# Transitest556-170113.net
KiCad netlist of a schematic drawn in EAGLE
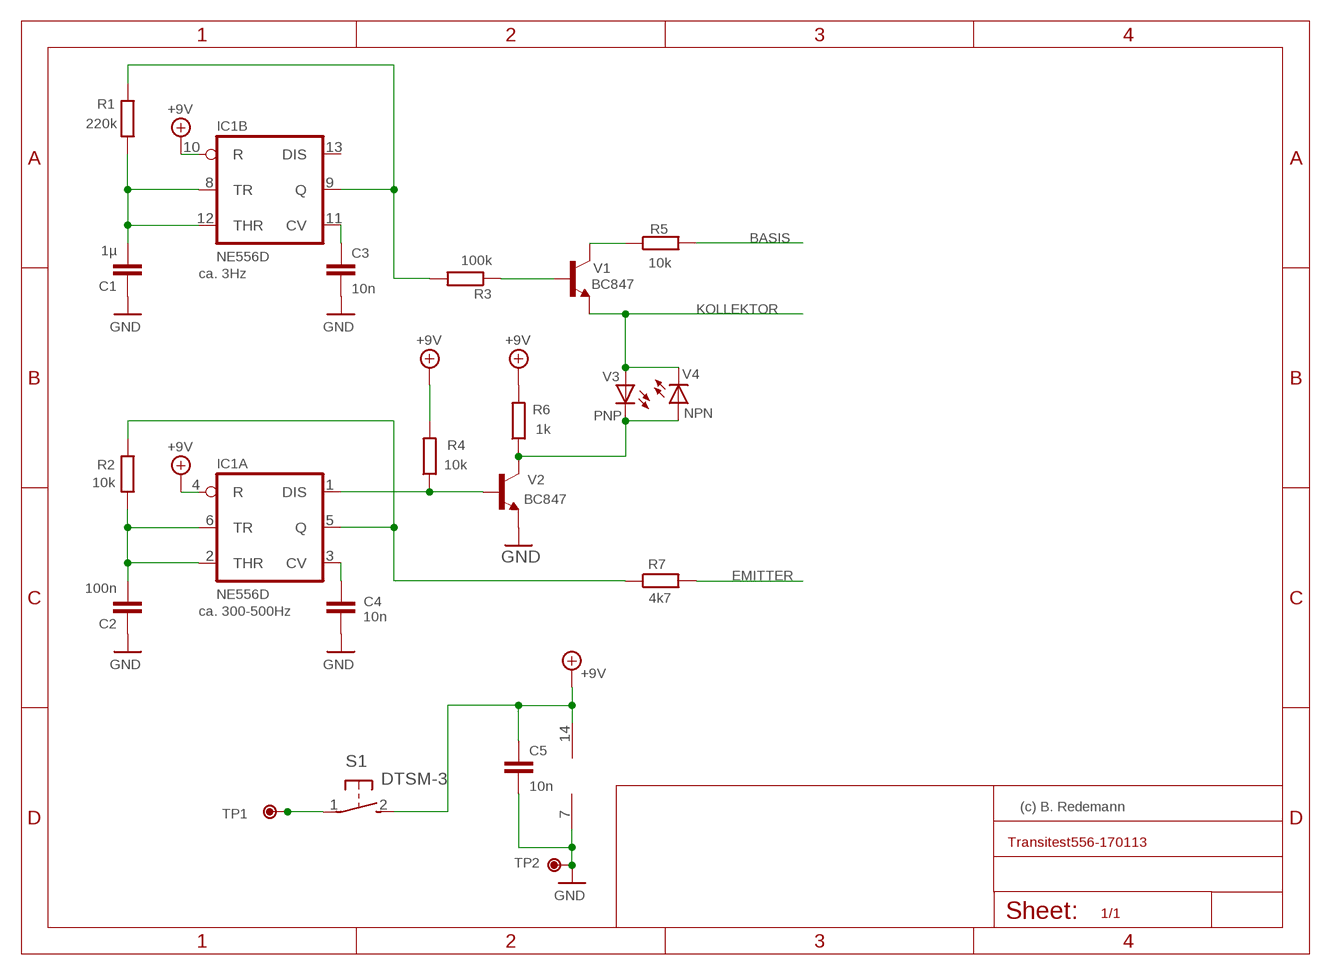
[diagram p0: schematic, sheet 1]

(export (version "E")
  (design (tool "Eeschema 10.0.6"))
  (components
    (comp (ref "C1")
      (value "1µ")
      (footprint "eagle-import:C0805")
      (libsource (lib "eagle-import") (part "C-EUC0805"))
    )
    (comp (ref "C2")
      (value "100n")
      (footprint "eagle-import:C0805")
      (libsource (lib "eagle-import") (part "C-EUC0805"))
    )
    (comp (ref "C3")
      (value "10n")
      (footprint "eagle-import:C0805")
      (libsource (lib "eagle-import") (part "C-EUC0805"))
    )
    (comp (ref "C4")
      (value "10n")
      (footprint "eagle-import:C0805")
      (libsource (lib "eagle-import") (part "C-EUC0805"))
    )
    (comp (ref "C5")
      (value "10n")
      (footprint "eagle-import:C0805")
      (libsource (lib "eagle-import") (part "C-EUC0805"))
    )
    (comp (ref "IC1")
      (value "NE556D")
      (footprint "eagle-import:SO14")
      (libsource (lib "eagle-import") (part "556DNE"))
    )
    (comp (ref "R1")
      (value "220k")
      (footprint "eagle-import:R0805")
      (libsource (lib "eagle-import") (part "R-EU_R0805"))
    )
    (comp (ref "R2")
      (value "10k")
      (footprint "eagle-import:R0805")
      (libsource (lib "eagle-import") (part "R-EU_R0805"))
    )
    (comp (ref "R3")
      (value "100k")
      (footprint "eagle-import:R0805")
      (libsource (lib "eagle-import") (part "R-EU_R0805"))
    )
    (comp (ref "R4")
      (value "10k")
      (footprint "eagle-import:R0805")
      (libsource (lib "eagle-import") (part "R-EU_R0805"))
    )
    (comp (ref "R5")
      (value "10k")
      (footprint "eagle-import:R0805")
      (libsource (lib "eagle-import") (part "R-EU_R0805"))
    )
    (comp (ref "R6")
      (value "1k")
      (footprint "eagle-import:R0805")
      (libsource (lib "eagle-import") (part "R-EU_R0805"))
    )
    (comp (ref "R7")
      (value "4k7")
      (footprint "eagle-import:R0805")
      (libsource (lib "eagle-import") (part "R-EU_R0805"))
    )
    (comp (ref "S1")
      (value "DTSM-3")
      (footprint "eagle-import:DTSM-3")
      (libsource (lib "eagle-import") (part "DTSM-3"))
    )
    (comp (ref "TP1")
      (value "TPPAD1-13")
      (footprint "eagle-import:P1-13")
      (libsource (lib "eagle-import") (part "TPPAD1-13"))
    )
    (comp (ref "TP2")
      (value "TPPAD1-13")
      (footprint "eagle-import:P1-13")
      (libsource (lib "eagle-import") (part "TPPAD1-13"))
    )
    (comp (ref "V1")
      (value "BC847")
      (footprint "eagle-import:SOT23")
      (libsource (lib "eagle-import") (part "BC847"))
    )
    (comp (ref "V2")
      (value "BC847")
      (footprint "eagle-import:SOT23")
      (libsource (lib "eagle-import") (part "BC847"))
    )
    (comp (ref "V3")
      (value "PNP")
      (footprint "eagle-import:CHIP-LED0805")
      (libsource (lib "eagle-import") (part "LEDCHIP-LED0805"))
    )
    (comp (ref "V4")
      (value "NPN")
      (footprint "eagle-import:CHIP-LED0805")
      (libsource (lib "eagle-import") (part "LEDCHIP-LED0805"))
    )
  )
  (nets
    (net (code "1") (name "+9V") (class "Default")
      (node (ref "C5") (pin "1") (pinfunction "1_1") (pintype "passive"))
      (node (ref "IC1") (pin "10") (pinfunction "R_10") (pintype "input"))
      (node (ref "IC1") (pin "14") (pinfunction "V+_14") (pintype "power_in"))
      (node (ref "IC1") (pin "4") (pinfunction "R_4") (pintype "input"))
      (node (ref "R4") (pin "2") (pinfunction "2_2") (pintype "passive"))
      (node (ref "R6") (pin "2") (pinfunction "2_2") (pintype "passive"))
      (node (ref "S1") (pin "2") (pinfunction "2_2") (pintype "passive"))
    )
    (net (code "2") (name "/BASIS") (class "Default")
      (node (ref "R5") (pin "2") (pinfunction "2_2") (pintype "passive"))
    )
    (net (code "3") (name "/EMITTER") (class "Default")
      (node (ref "R7") (pin "2") (pinfunction "2_2") (pintype "passive"))
    )
    (net (code "4") (name "/KOLLEKTOR") (class "Default")
      (node (ref "V1") (pin "2") (pinfunction "E_2") (pintype "passive"))
      (node (ref "V3") (pin "A") (pinfunction "A_A") (pintype "passive"))
      (node (ref "V4") (pin "C") (pinfunction "C_C") (pintype "passive"))
    )
    (net (code "5") (name "GND") (class "Default")
      (node (ref "C1") (pin "1") (pinfunction "1_1") (pintype "passive"))
      (node (ref "C2") (pin "1") (pinfunction "1_1") (pintype "passive"))
      (node (ref "C3") (pin "2") (pinfunction "2_2") (pintype "passive"))
      (node (ref "C4") (pin "1") (pinfunction "1_1") (pintype "passive"))
      (node (ref "C5") (pin "2") (pinfunction "2_2") (pintype "passive"))
      (node (ref "IC1") (pin "7") (pinfunction "GND_7") (pintype "power_in"))
      (node (ref "TP2") (pin "TP") (pinfunction "TP_TP") (pintype "bidirectional"))
      (node (ref "V2") (pin "2") (pinfunction "E_2") (pintype "passive"))
    )
    (net (code "6") (name "Net-(IC1A-CV)") (class "Default")
      (node (ref "C4") (pin "2") (pinfunction "2_2") (pintype "passive"))
      (node (ref "IC1") (pin "3") (pinfunction "CV_3") (pintype "bidirectional"))
    )
    (net (code "7") (name "Net-(IC1A-DIS)") (class "Default")
      (node (ref "IC1") (pin "1") (pinfunction "DIS_1") (pintype "output"))
      (node (ref "R4") (pin "1") (pinfunction "1_1") (pintype "passive"))
      (node (ref "V2") (pin "1") (pinfunction "B_1") (pintype "passive"))
    )
    (net (code "8") (name "Net-(IC1A-Q)") (class "Default")
      (node (ref "IC1") (pin "5") (pinfunction "Q_5") (pintype "output"))
      (node (ref "R2") (pin "2") (pinfunction "2_2") (pintype "passive"))
      (node (ref "R7") (pin "1") (pinfunction "1_1") (pintype "passive"))
    )
    (net (code "9") (name "Net-(IC1A-THR)") (class "Default")
      (node (ref "C2") (pin "2") (pinfunction "2_2") (pintype "passive"))
      (node (ref "IC1") (pin "2") (pinfunction "THR_2") (pintype "input"))
      (node (ref "IC1") (pin "6") (pinfunction "TR_6") (pintype "input"))
      (node (ref "R2") (pin "1") (pinfunction "1_1") (pintype "passive"))
    )
    (net (code "10") (name "Net-(IC1B-CV)") (class "Default")
      (node (ref "C3") (pin "1") (pinfunction "1_1") (pintype "passive"))
      (node (ref "IC1") (pin "11") (pinfunction "CV_11") (pintype "bidirectional"))
    )
    (net (code "11") (name "Net-(IC1B-Q)") (class "Default")
      (node (ref "IC1") (pin "9") (pinfunction "Q_9") (pintype "output"))
      (node (ref "R1") (pin "2") (pinfunction "2_2") (pintype "passive"))
      (node (ref "R3") (pin "2") (pinfunction "2_2") (pintype "passive"))
    )
    (net (code "12") (name "Net-(IC1B-THR)") (class "Default")
      (node (ref "C1") (pin "2") (pinfunction "2_2") (pintype "passive"))
      (node (ref "IC1") (pin "12") (pinfunction "THR_12") (pintype "input"))
      (node (ref "IC1") (pin "8") (pinfunction "TR_8") (pintype "input"))
      (node (ref "R1") (pin "1") (pinfunction "1_1") (pintype "passive"))
    )
    (net (code "13") (name "Net-(S1-Pad1)") (class "Default")
      (node (ref "S1") (pin "1") (pinfunction "1_1") (pintype "passive"))
      (node (ref "TP1") (pin "TP") (pinfunction "TP_TP") (pintype "bidirectional"))
    )
    (net (code "14") (name "Net-(V1-B)") (class "Default")
      (node (ref "R3") (pin "1") (pinfunction "1_1") (pintype "passive"))
      (node (ref "V1") (pin "1") (pinfunction "B_1") (pintype "passive"))
    )
    (net (code "15") (name "Net-(V1-C)") (class "Default")
      (node (ref "R5") (pin "1") (pinfunction "1_1") (pintype "passive"))
      (node (ref "V1") (pin "3") (pinfunction "C_3") (pintype "passive"))
    )
    (net (code "16") (name "Net-(V2-C)") (class "Default")
      (node (ref "R6") (pin "1") (pinfunction "1_1") (pintype "passive"))
      (node (ref "V2") (pin "3") (pinfunction "C_3") (pintype "passive"))
      (node (ref "V3") (pin "C") (pinfunction "C_C") (pintype "passive"))
      (node (ref "V4") (pin "A") (pinfunction "A_A") (pintype "passive"))
    )
    (net (code "17") (name "unconnected-(IC1B-DIS-Pad13)") (class "Default")
      (node (ref "IC1") (pin "13") (pinfunction "DIS_13") (pintype "output"))
    )
  )
)
